# PressureSensor1.net
KiCad netlist of a schematic drawn in Altium Designer
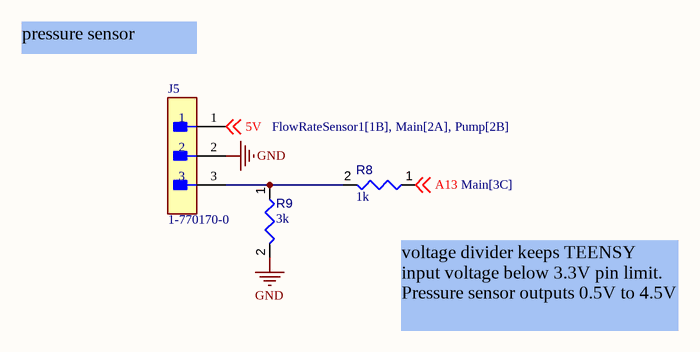
[diagram p0: PressureSensor1.SchDoc]

(export (version "E")
  (design (tool "Eeschema 10.0.6"))
  (components
    (comp (ref "J5")
      (value "1-770170-0")
      (footprint "FP-1-770170-0-MFG")
      (description "CONN HEADER VERT 3POS 4.14MM")
      (fields
        (field (name "OCTOPART") "https://octopart.com/1-770170-0-te+connectivity-46505214")
        (field (name "MANUFACTURER") "TE Connectivity")
      )
      (libsource (lib "Altium Content Vault") (part "0d3f023dd272f625e17a2be33dea85f"))
    )
    (comp (ref "R8")
      (value "1k")
      (footprint "RESC0402(1005)_L")
      (description "1K 0.063W 5% 0402 (1005 Metric)  SMD")
      (fields (field (name "POWER") "63mW") (field (name "TOLERANCE") "5%"))
      (libsource (lib "Alt_ium Course") (part "1KR2J"))
    )
    (comp (ref "R9")
      (value "3k")
      (footprint "RESC0402(1005)_L")
      (description "3K 0.063W 1% 0402 (1005 Metric)  SMD")
      (fields (field (name "POWER") "63mW") (field (name "TOLERANCE") "1%"))
      (libsource (lib "Alt_ium Course") (part "3KR2F"))
    )
  )
  (nets
    (net (code "1") (name "5V") (class "Default")
      (node (ref "J5") (pin "1") (pinfunction "1_1") (pintype "passive"))
    )
    (net (code "2") (name "A13") (class "Default")
      (node (ref "R8") (pin "1") (pinfunction "1_1") (pintype "passive"))
    )
    (net (code "3") (name "GND") (class "Default")
      (node (ref "J5") (pin "2") (pinfunction "2_2") (pintype "passive"))
      (node (ref "R9") (pin "2") (pinfunction "2_2") (pintype "passive"))
    )
    (net (code "4") (name "Net-(J5-Pad3)") (class "Default")
      (node (ref "J5") (pin "3") (pinfunction "3_3") (pintype "passive"))
      (node (ref "R8") (pin "2") (pinfunction "2_2") (pintype "passive"))
      (node (ref "R9") (pin "1") (pinfunction "1_1") (pintype "passive"))
    )
  )
)
